# USBHUB2_0.net
KiCad netlist of a schematic drawn in EasyEDA Pro
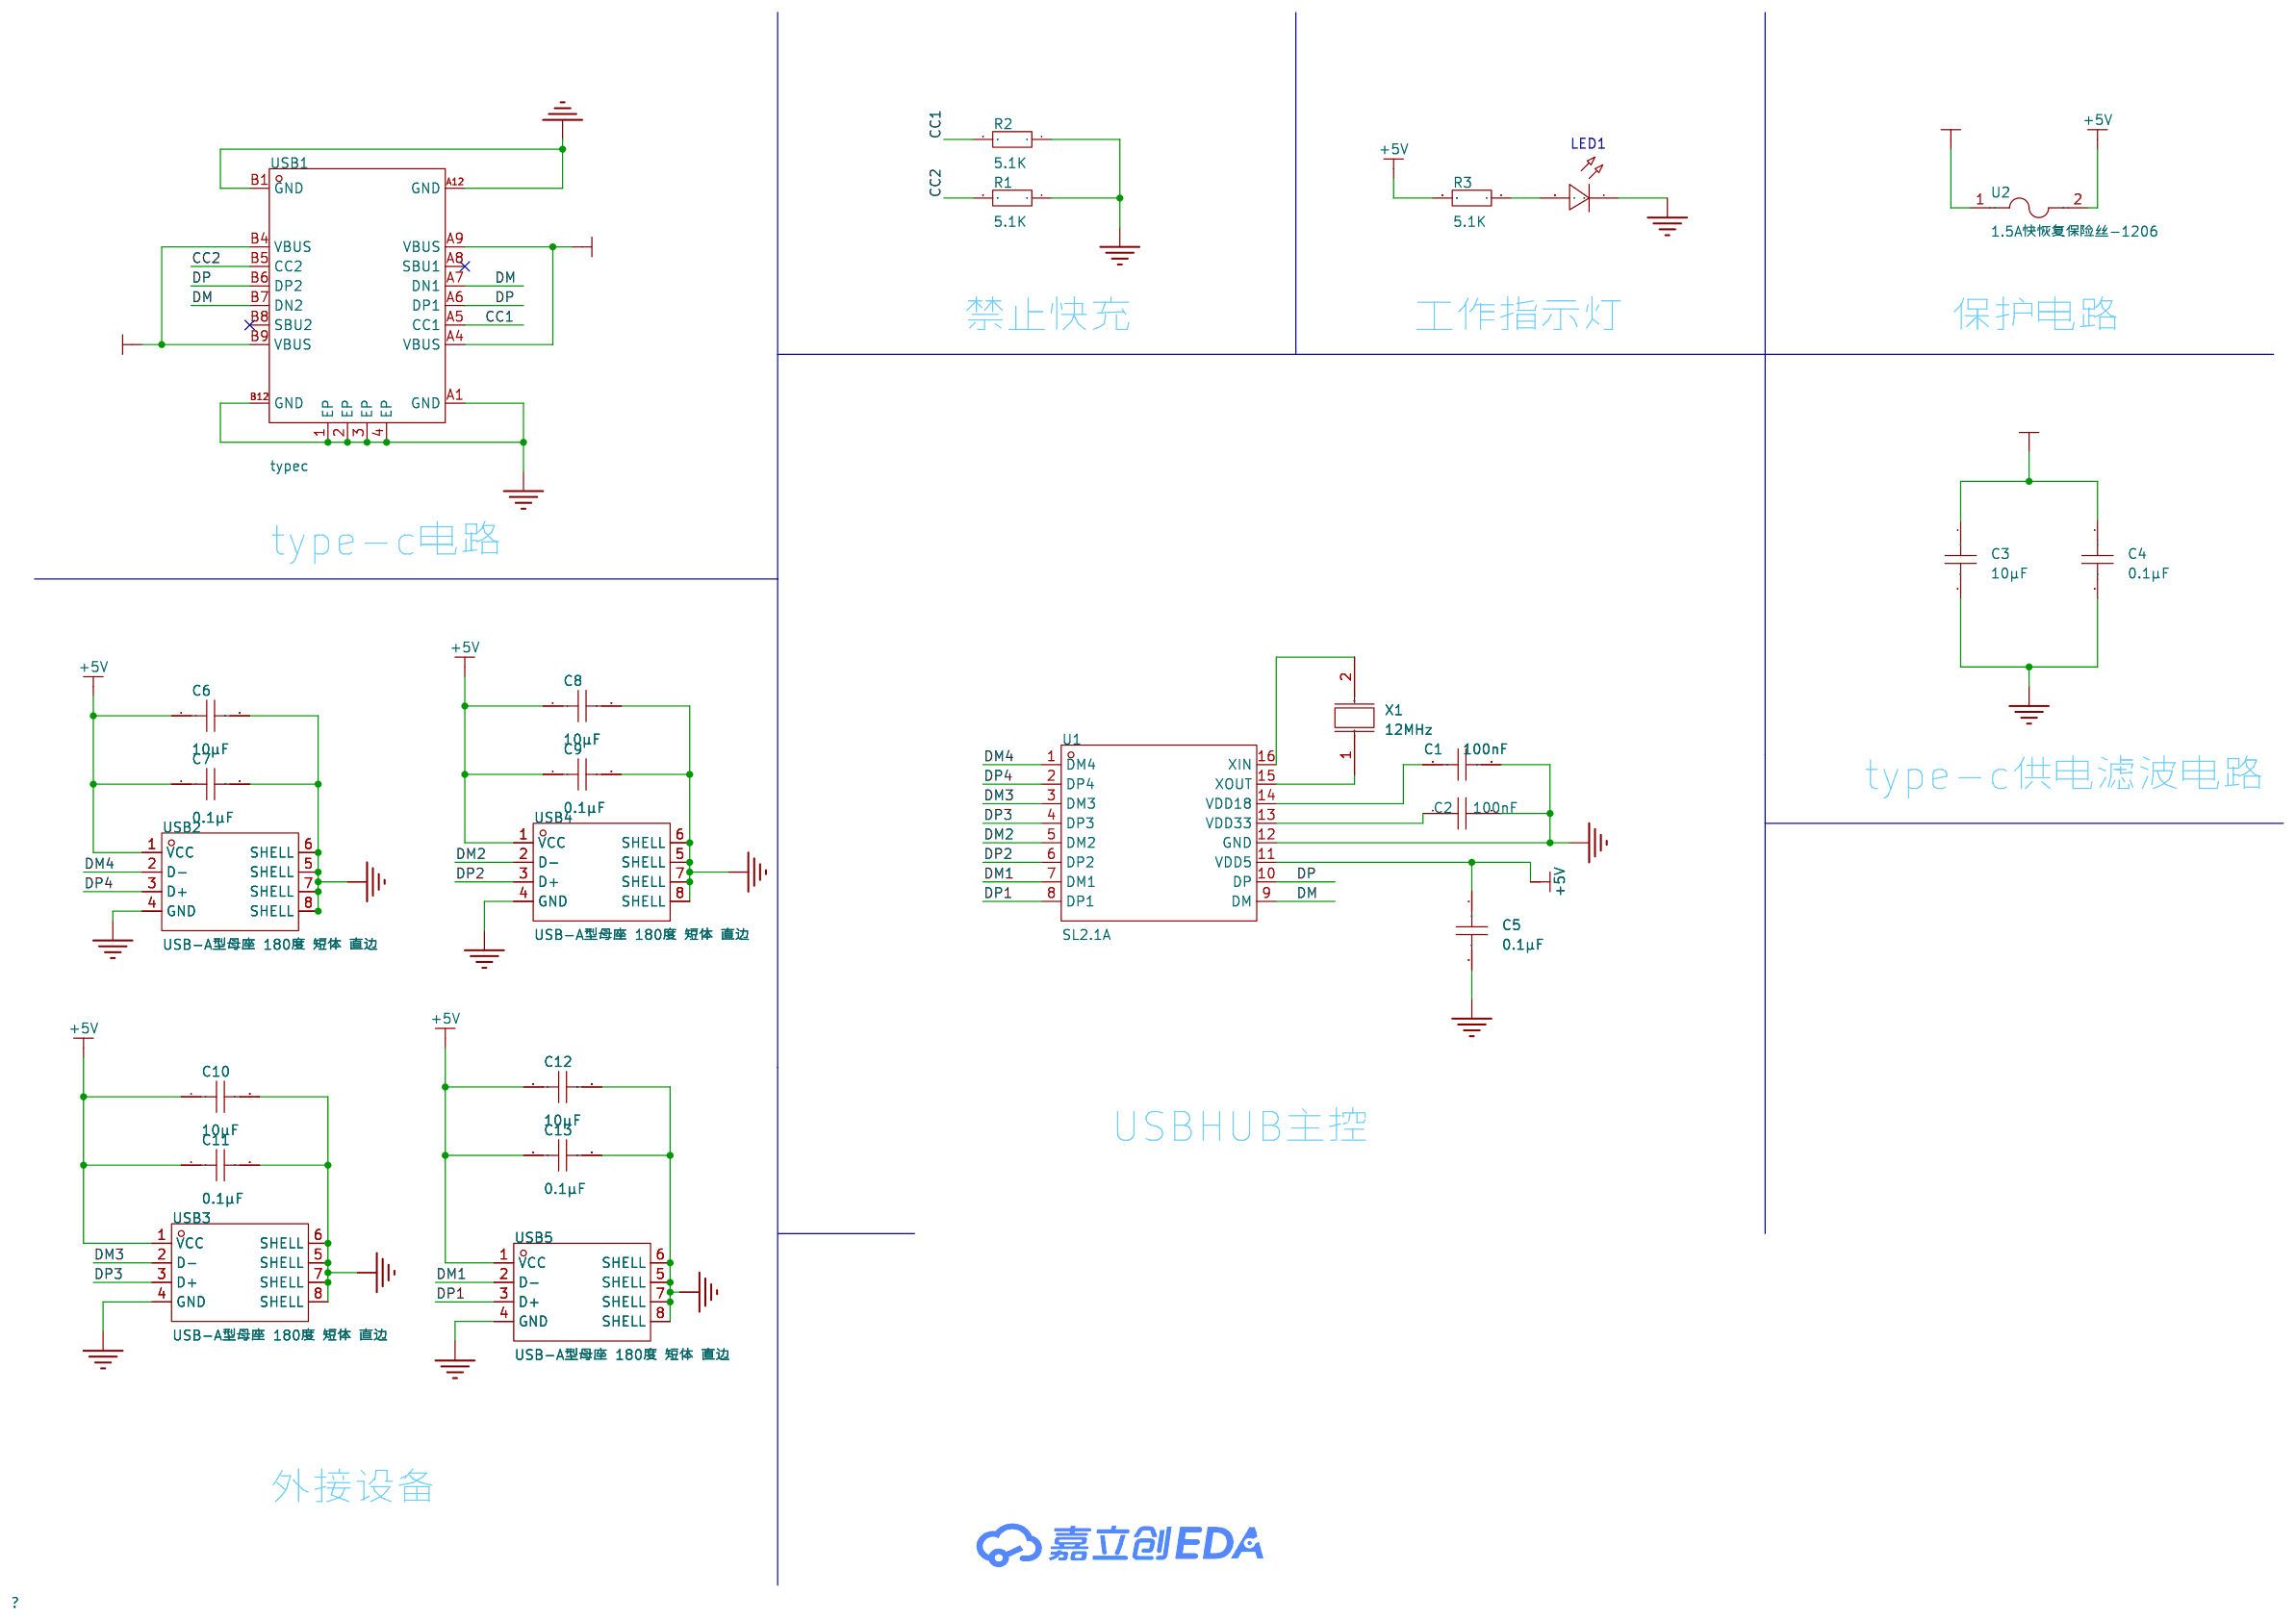
[diagram p0: schematic sheet]

(export (version "E")
  (design (tool "Eeschema 10.0.6"))
  (components
    (comp (ref "C1")
      (value "100nF")
      (footprint "easyedapro:C0805")
      (libsource (lib "easyedapro") (part "CapAcitance"))
    )
    (comp (ref "C2")
      (value "100nF")
      (footprint "easyedapro:C0805")
      (libsource (lib "easyedapro") (part "CapAcitance"))
    )
    (comp (ref "C3")
      (value "10μF")
      (footprint "easyedapro:C0805")
      (libsource (lib "easyedapro") (part "CapAcitance"))
    )
    (comp (ref "C4")
      (value "0.1μF")
      (footprint "easyedapro:C0805")
      (libsource (lib "easyedapro") (part "CapAcitance"))
    )
    (comp (ref "C5")
      (value "0.1μF")
      (footprint "easyedapro:C0805")
      (libsource (lib "easyedapro") (part "CapAcitance"))
    )
    (comp (ref "C6")
      (value "10μF")
      (footprint "easyedapro:C0805")
      (libsource (lib "easyedapro") (part "CapAcitance"))
    )
    (comp (ref "C7")
      (value "0.1μF")
      (footprint "easyedapro:C0805")
      (libsource (lib "easyedapro") (part "CapAcitance"))
    )
    (comp (ref "C8")
      (value "10μF")
      (footprint "easyedapro:C0805")
      (libsource (lib "easyedapro") (part "CapAcitance"))
    )
    (comp (ref "C9")
      (value "0.1μF")
      (footprint "easyedapro:C0805")
      (libsource (lib "easyedapro") (part "CapAcitance"))
    )
    (comp (ref "C10")
      (value "10μF")
      (footprint "easyedapro:C0805")
      (libsource (lib "easyedapro") (part "CapAcitance"))
    )
    (comp (ref "C11")
      (value "0.1μF")
      (footprint "easyedapro:C0805")
      (libsource (lib "easyedapro") (part "CapAcitance"))
    )
    (comp (ref "C12")
      (value "10μF")
      (footprint "easyedapro:C0805")
      (libsource (lib "easyedapro") (part "CapAcitance"))
    )
    (comp (ref "C13")
      (value "0.1μF")
      (footprint "easyedapro:C0805")
      (libsource (lib "easyedapro") (part "CapAcitance"))
    )
    (comp (ref "LED1")
      (value "~")
      (footprint "easyedapro:LED_0603")
      (libsource (lib "easyedapro") (part "LED_G"))
    )
    (comp (ref "R1") (value "5.1K") (footprint "easyedapro:R0805") (libsource (lib "easyedapro") (part "电阻")))
    (comp (ref "R2") (value "5.1K") (footprint "easyedapro:R0805") (libsource (lib "easyedapro") (part "电阻")))
    (comp (ref "R3") (value "5.1K") (footprint "easyedapro:R0805") (libsource (lib "easyedapro") (part "电阻")))
    (comp (ref "U1")
      (value "SL2.1A")
      (footprint "easyedapro:SOP-16_L10.0-W3.9-P1.27-LS6.0-BL")
      (fields (field (name "Manufacturer") "CoreChips(和芯润德)"))
      (libsource (lib "easyedapro") (part "SL2.1A_C6798314"))
    )
    (comp (ref "U2")
      (value "1.5A快恢复保险丝-1206")
      (footprint "easyedapro:F1206")
      (libsource (lib "easyedapro") (part "1.5A快恢复保险丝-1206"))
    )
    (comp (ref "USB1")
      (value "typec")
      (footprint "easyedapro:USB-C-SMD_KH-TYPE-C-16P")
      (libsource (lib "easyedapro") (part "TYPEC_C9900016956"))
    )
    (comp (ref "USB2")
      (value "USB-A型母座 180度 短体 直边")
      (footprint "easyedapro:USB-A-SMD_WT_C9900004571")
      (libsource (lib "easyedapro") (part "USB-A型母座 180度 短体 直边"))
    )
    (comp (ref "USB3")
      (value "USB-A型母座 180度 短体 直边")
      (footprint "easyedapro:USB-A-SMD_WT_C9900004571")
      (libsource (lib "easyedapro") (part "USB-A型母座 180度 短体 直边"))
    )
    (comp (ref "USB4")
      (value "USB-A型母座 180度 短体 直边")
      (footprint "easyedapro:USB-A-SMD_WT_C9900004571")
      (libsource (lib "easyedapro") (part "USB-A型母座 180度 短体 直边"))
    )
    (comp (ref "USB5")
      (value "USB-A型母座 180度 短体 直边")
      (footprint "easyedapro:USB-A-SMD_WT_C9900004571")
      (libsource (lib "easyedapro") (part "USB-A型母座 180度 短体 直边"))
    )
    (comp (ref "X1")
      (value "12MHz")
      (footprint "easyedapro:CRYSTAL-SMD_L5.0-W3.2-1-A")
      (description "晶振类型:贴片晶振;频率:12MHz;常温频差:±20ppm;外接负载电容:20pF;")
      (fields (field (name "Manufacturer Part") "G5312000202090") (field (name "Manufacturer") "JGHC(晶光华)"))
      (libsource (lib "easyedapro") (part "G5312000202090"))
    )
  )
  (nets
    (net (code "1") (name "+5V") (class "Default")
      (node (ref "C10") (pin "1") (pinfunction "1_1") (pintype "input"))
      (node (ref "C11") (pin "1") (pinfunction "1_1") (pintype "input"))
      (node (ref "C12") (pin "1") (pinfunction "1_1") (pintype "input"))
      (node (ref "C13") (pin "1") (pinfunction "1_1") (pintype "input"))
      (node (ref "C5") (pin "1") (pinfunction "1_1") (pintype "input"))
      (node (ref "C6") (pin "1") (pinfunction "1_1") (pintype "input"))
      (node (ref "C7") (pin "1") (pinfunction "1_1") (pintype "input"))
      (node (ref "C8") (pin "1") (pinfunction "1_1") (pintype "input"))
      (node (ref "C9") (pin "1") (pinfunction "1_1") (pintype "input"))
      (node (ref "R3") (pin "2") (pinfunction "2_2") (pintype "input"))
      (node (ref "U1") (pin "11") (pinfunction "VDD5_11") (pintype "unspecified"))
      (node (ref "U2") (pin "2") (pinfunction "2_2") (pintype "unspecified"))
      (node (ref "USB2") (pin "1") (pinfunction "VCC_1") (pintype "unspecified"))
      (node (ref "USB3") (pin "1") (pinfunction "VCC_1") (pintype "unspecified"))
      (node (ref "USB4") (pin "1") (pinfunction "VCC_1") (pintype "unspecified"))
      (node (ref "USB5") (pin "1") (pinfunction "VCC_1") (pintype "unspecified"))
    )
    (net (code "2") (name "/CC1") (class "Default")
      (node (ref "R2") (pin "2") (pinfunction "2_2") (pintype "input"))
      (node (ref "USB1") (pin "A5") (pinfunction "CC1_A5") (pintype "unspecified"))
    )
    (net (code "3") (name "/CC2") (class "Default")
      (node (ref "R1") (pin "2") (pinfunction "2_2") (pintype "input"))
      (node (ref "USB1") (pin "B5") (pinfunction "CC2_B5") (pintype "unspecified"))
    )
    (net (code "4") (name "/DM") (class "Default")
      (node (ref "U1") (pin "9") (pinfunction "DM_9") (pintype "unspecified"))
      (node (ref "USB1") (pin "A7") (pinfunction "DN1_A7") (pintype "unspecified"))
      (node (ref "USB1") (pin "B7") (pinfunction "DN2_B7") (pintype "unspecified"))
    )
    (net (code "5") (name "/DM1") (class "Default")
      (node (ref "U1") (pin "7") (pinfunction "DM1_7") (pintype "unspecified"))
      (node (ref "USB5") (pin "2") (pinfunction "D-_2") (pintype "unspecified"))
    )
    (net (code "6") (name "/DM2") (class "Default")
      (node (ref "U1") (pin "5") (pinfunction "DM2_5") (pintype "unspecified"))
      (node (ref "USB4") (pin "2") (pinfunction "D-_2") (pintype "unspecified"))
    )
    (net (code "7") (name "/DM3") (class "Default")
      (node (ref "U1") (pin "3") (pinfunction "DM3_3") (pintype "unspecified"))
      (node (ref "USB3") (pin "2") (pinfunction "D-_2") (pintype "unspecified"))
    )
    (net (code "8") (name "/DM4") (class "Default")
      (node (ref "U1") (pin "1") (pinfunction "DM4_1") (pintype "unspecified"))
      (node (ref "USB2") (pin "2") (pinfunction "D-_2") (pintype "unspecified"))
    )
    (net (code "9") (name "/DP") (class "Default")
      (node (ref "U1") (pin "10") (pinfunction "DP_10") (pintype "unspecified"))
      (node (ref "USB1") (pin "A6") (pinfunction "DP1_A6") (pintype "unspecified"))
      (node (ref "USB1") (pin "B6") (pinfunction "DP2_B6") (pintype "unspecified"))
    )
    (net (code "10") (name "/DP1") (class "Default")
      (node (ref "U1") (pin "8") (pinfunction "DP1_8") (pintype "unspecified"))
      (node (ref "USB5") (pin "3") (pinfunction "D+_3") (pintype "unspecified"))
    )
    (net (code "11") (name "/DP2") (class "Default")
      (node (ref "U1") (pin "6") (pinfunction "DP2_6") (pintype "unspecified"))
      (node (ref "USB4") (pin "3") (pinfunction "D+_3") (pintype "unspecified"))
    )
    (net (code "12") (name "/DP3") (class "Default")
      (node (ref "U1") (pin "4") (pinfunction "DP3_4") (pintype "unspecified"))
      (node (ref "USB3") (pin "3") (pinfunction "D+_3") (pintype "unspecified"))
    )
    (net (code "13") (name "/DP4") (class "Default")
      (node (ref "U1") (pin "2") (pinfunction "DP4_2") (pintype "unspecified"))
      (node (ref "USB2") (pin "3") (pinfunction "D+_3") (pintype "unspecified"))
    )
    (net (code "14") (name "GND") (class "Default")
      (node (ref "C1") (pin "2") (pinfunction "2_2") (pintype "input"))
      (node (ref "C10") (pin "2") (pinfunction "2_2") (pintype "input"))
      (node (ref "C11") (pin "2") (pinfunction "2_2") (pintype "input"))
      (node (ref "C12") (pin "2") (pinfunction "2_2") (pintype "input"))
      (node (ref "C13") (pin "2") (pinfunction "2_2") (pintype "input"))
      (node (ref "C2") (pin "2") (pinfunction "2_2") (pintype "input"))
      (node (ref "C3") (pin "2") (pinfunction "2_2") (pintype "input"))
      (node (ref "C4") (pin "2") (pinfunction "2_2") (pintype "input"))
      (node (ref "C5") (pin "2") (pinfunction "2_2") (pintype "input"))
      (node (ref "C6") (pin "2") (pinfunction "2_2") (pintype "input"))
      (node (ref "C7") (pin "2") (pinfunction "2_2") (pintype "input"))
      (node (ref "C8") (pin "2") (pinfunction "2_2") (pintype "input"))
      (node (ref "C9") (pin "2") (pinfunction "2_2") (pintype "input"))
      (node (ref "LED1") (pin "1") (pinfunction "C_1") (pintype "input"))
      (node (ref "R1") (pin "1") (pinfunction "1_1") (pintype "input"))
      (node (ref "R2") (pin "1") (pinfunction "1_1") (pintype "input"))
      (node (ref "U1") (pin "12") (pinfunction "GND_12") (pintype "unspecified"))
      (node (ref "USB1") (pin "1") (pinfunction "EP_1") (pintype "unspecified"))
      (node (ref "USB1") (pin "2") (pinfunction "EP_2") (pintype "unspecified"))
      (node (ref "USB1") (pin "3") (pinfunction "EP_3") (pintype "unspecified"))
      (node (ref "USB1") (pin "4") (pinfunction "EP_4") (pintype "unspecified"))
      (node (ref "USB1") (pin "A1") (pinfunction "GND_A1") (pintype "unspecified"))
      (node (ref "USB1") (pin "A12") (pinfunction "GND_A12") (pintype "unspecified"))
      (node (ref "USB1") (pin "B1") (pinfunction "GND_B1") (pintype "unspecified"))
      (node (ref "USB1") (pin "B12") (pinfunction "GND_B12") (pintype "unspecified"))
      (node (ref "USB2") (pin "4") (pinfunction "GND_4") (pintype "unspecified"))
      (node (ref "USB2") (pin "5") (pinfunction "SHELL_5") (pintype "unspecified"))
      (node (ref "USB2") (pin "6") (pinfunction "SHELL_6") (pintype "unspecified"))
      (node (ref "USB2") (pin "7") (pinfunction "SHELL_7") (pintype "unspecified"))
      (node (ref "USB2") (pin "8") (pinfunction "SHELL_8") (pintype "unspecified"))
      (node (ref "USB3") (pin "4") (pinfunction "GND_4") (pintype "unspecified"))
      (node (ref "USB3") (pin "5") (pinfunction "SHELL_5") (pintype "unspecified"))
      (node (ref "USB3") (pin "6") (pinfunction "SHELL_6") (pintype "unspecified"))
      (node (ref "USB3") (pin "7") (pinfunction "SHELL_7") (pintype "unspecified"))
      (node (ref "USB3") (pin "8") (pinfunction "SHELL_8") (pintype "unspecified"))
      (node (ref "USB4") (pin "4") (pinfunction "GND_4") (pintype "unspecified"))
      (node (ref "USB4") (pin "5") (pinfunction "SHELL_5") (pintype "unspecified"))
      (node (ref "USB4") (pin "6") (pinfunction "SHELL_6") (pintype "unspecified"))
      (node (ref "USB4") (pin "7") (pinfunction "SHELL_7") (pintype "unspecified"))
      (node (ref "USB4") (pin "8") (pinfunction "SHELL_8") (pintype "unspecified"))
      (node (ref "USB5") (pin "4") (pinfunction "GND_4") (pintype "unspecified"))
      (node (ref "USB5") (pin "5") (pinfunction "SHELL_5") (pintype "unspecified"))
      (node (ref "USB5") (pin "6") (pinfunction "SHELL_6") (pintype "unspecified"))
      (node (ref "USB5") (pin "7") (pinfunction "SHELL_7") (pintype "unspecified"))
      (node (ref "USB5") (pin "8") (pinfunction "SHELL_8") (pintype "unspecified"))
    )
    (net (code "15") (name "Net-(LED1-A)") (class "Default")
      (node (ref "LED1") (pin "2") (pinfunction "A_2") (pintype "input"))
      (node (ref "R3") (pin "1") (pinfunction "1_1") (pintype "input"))
    )
    (net (code "16") (name "Net-(U1-VDD18)") (class "Default")
      (node (ref "C1") (pin "1") (pinfunction "1_1") (pintype "input"))
      (node (ref "U1") (pin "14") (pinfunction "VDD18_14") (pintype "unspecified"))
    )
    (net (code "17") (name "Net-(U1-VDD33)") (class "Default")
      (node (ref "C2") (pin "1") (pinfunction "1_1") (pintype "input"))
      (node (ref "U1") (pin "13") (pinfunction "VDD33_13") (pintype "unspecified"))
    )
    (net (code "18") (name "Net-(U1-XIN)") (class "Default")
      (node (ref "U1") (pin "16") (pinfunction "XIN_16") (pintype "unspecified"))
      (node (ref "X1") (pin "2") (pinfunction "2_2") (pintype "unspecified"))
    )
    (net (code "19") (name "Net-(U1-XOUT)") (class "Default")
      (node (ref "U1") (pin "15") (pinfunction "XOUT_15") (pintype "unspecified"))
      (node (ref "X1") (pin "1") (pinfunction "1_1") (pintype "unspecified"))
    )
    (net (code "20") (name "VCC+5V") (class "Default")
      (node (ref "C3") (pin "1") (pinfunction "1_1") (pintype "input"))
      (node (ref "C4") (pin "1") (pinfunction "1_1") (pintype "input"))
      (node (ref "U2") (pin "1") (pinfunction "1_1") (pintype "unspecified"))
      (node (ref "USB1") (pin "A4") (pinfunction "VBUS_A4") (pintype "unspecified"))
      (node (ref "USB1") (pin "A9") (pinfunction "VBUS_A9") (pintype "unspecified"))
      (node (ref "USB1") (pin "B4") (pinfunction "VBUS_B4") (pintype "unspecified"))
      (node (ref "USB1") (pin "B9") (pinfunction "VBUS_B9") (pintype "unspecified"))
    )
    (net (code "21") (name "unconnected-(USB1-SBU1-PadA8)") (class "Default")
      (node (ref "USB1") (pin "A8") (pinfunction "SBU1_A8") (pintype "unspecified+no_connect"))
    )
    (net (code "22") (name "unconnected-(USB1-SBU2-PadB8)") (class "Default")
      (node (ref "USB1") (pin "B8") (pinfunction "SBU2_B8") (pintype "unspecified+no_connect"))
    )
  )
)
